# SCH_Selectric-Conversion_2024-07-05.net
KiCad netlist of a schematic drawn in EasyEDA
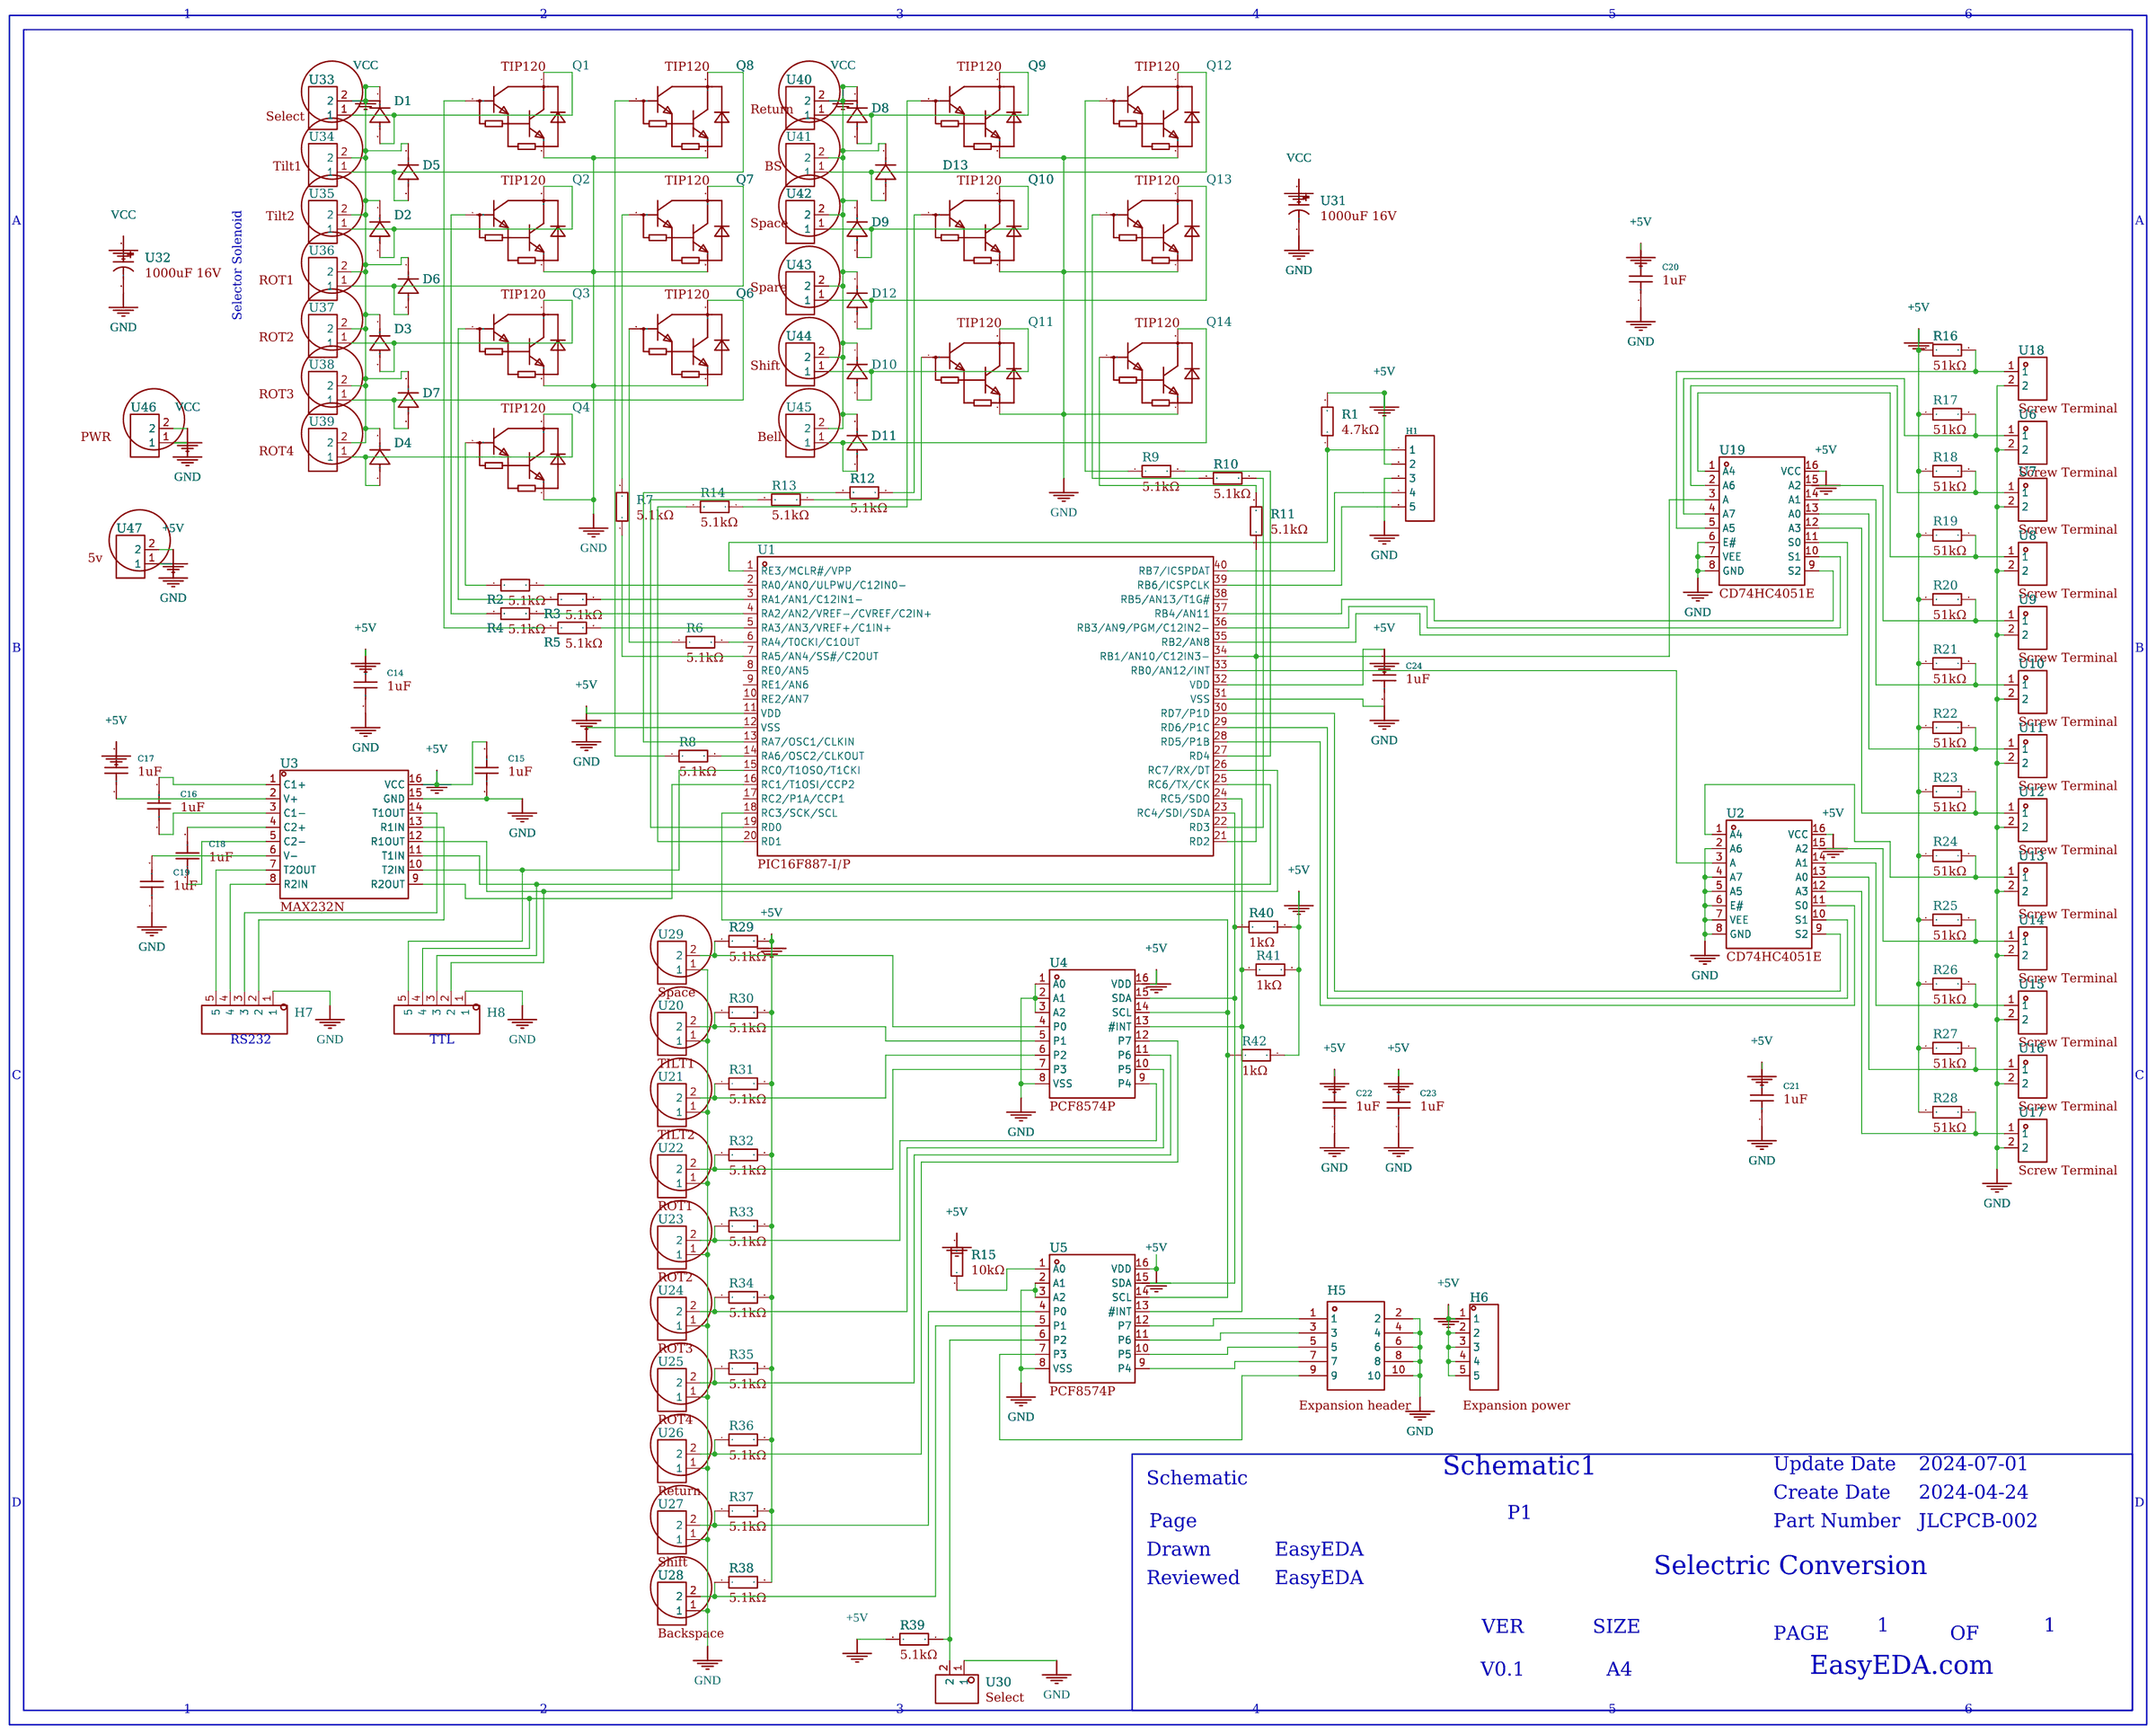
[diagram p0: schematic sheet]

(export (version "E")
  (design (tool "Eeschema 10.0.6"))
  (components
    (comp (ref "C14")
      (value "1uF")
      (fields
        (field (name "Manufacturer Part") "CC1H104MC1FD3F6C10MF")
        (field (name "Manufacturer") "Dersonic(德尔创)")
      )
      (libsource (lib "") (part "Unknown_280_-760"))
    )
    (comp (ref "C15")
      (value "1uF")
      (fields
        (field (name "Manufacturer Part") "CC1H104MC1FD3F6C10MF")
        (field (name "Manufacturer") "Dersonic(德尔创)")
      )
      (libsource (lib "") (part "Unknown_365_-700"))
    )
    (comp (ref "C16")
      (value "1uF")
      (fields
        (field (name "Manufacturer Part") "CC1H104MC1FD3F6C10MF")
        (field (name "Manufacturer") "Dersonic(德尔创)")
      )
      (libsource (lib "") (part "Unknown_135_-675"))
    )
    (comp (ref "C17")
      (value "1uF")
      (fields
        (field (name "Manufacturer Part") "CC1H104MC1FD3F6C10MF")
        (field (name "Manufacturer") "Dersonic(德尔创)")
      )
      (libsource (lib "") (part "Unknown_105_-700"))
    )
    (comp (ref "C18")
      (value "1uF")
      (fields
        (field (name "Manufacturer Part") "CC1H104MC1FD3F6C10MF")
        (field (name "Manufacturer") "Dersonic(德尔创)")
      )
      (libsource (lib "") (part "Unknown_155_-640"))
    )
    (comp (ref "C19")
      (value "1uF")
      (fields
        (field (name "Manufacturer Part") "CC1H104MC1FD3F6C10MF")
        (field (name "Manufacturer") "Dersonic(德尔创)")
      )
      (libsource (lib "") (part "Unknown_130_-620"))
    )
    (comp (ref "C20")
      (value "1uF")
      (fields
        (field (name "Manufacturer Part") "CC1H104MC1FD3F6C10MF")
        (field (name "Manufacturer") "Dersonic(德尔创)")
      )
      (libsource (lib "") (part "Unknown_1175_-1045"))
    )
    (comp (ref "C21")
      (value "1uF")
      (fields
        (field (name "Manufacturer Part") "CC1H104MC1FD3F6C10MF")
        (field (name "Manufacturer") "Dersonic(德尔创)")
      )
      (libsource (lib "") (part "Unknown_1260_-470"))
    )
    (comp (ref "C22")
      (value "1uF")
      (fields
        (field (name "Manufacturer Part") "CC1H104MC1FD3F6C10MF")
        (field (name "Manufacturer") "Dersonic(德尔创)")
      )
      (libsource (lib "") (part "Unknown_960_-465"))
    )
    (comp (ref "C23")
      (value "1uF")
      (fields
        (field (name "Manufacturer Part") "CC1H104MC1FD3F6C10MF")
        (field (name "Manufacturer") "Dersonic(德尔创)")
      )
      (libsource (lib "") (part "Unknown_1005_-465"))
    )
    (comp (ref "C24")
      (value "1uF")
      (fields
        (field (name "Manufacturer Part") "CC1H104MC1FD3F6C10MF")
        (field (name "Manufacturer") "Dersonic(德尔创)")
      )
      (libsource (lib "") (part "Unknown_995_-765"))
    )
    (comp (ref "D1") (value "1N4007") (libsource (lib "") (part "Unknown_290_-1160")))
    (comp (ref "D2") (value "1N4007") (libsource (lib "") (part "Unknown_290_-1080")))
    (comp (ref "D3") (value "1N4007") (libsource (lib "") (part "Unknown_290_-1000")))
    (comp (ref "D4") (value "1N4007") (libsource (lib "") (part "Unknown_290_-920")))
    (comp (ref "D5") (value "1N4007") (libsource (lib "") (part "Unknown_310_-1120")))
    (comp (ref "D6") (value "1N4007") (libsource (lib "") (part "Unknown_310_-1040")))
    (comp (ref "D7") (value "1N4007") (libsource (lib "") (part "Unknown_310_-960")))
    (comp (ref "D8") (value "1N4007") (libsource (lib "") (part "Unknown_625_-1160")))
    (comp (ref "D9") (value "1N4007") (libsource (lib "") (part "Unknown_625_-1080")))
    (comp (ref "D10") (value "1N4007") (libsource (lib "") (part "Unknown_625_-980")))
    (comp (ref "D11") (value "1N4007") (libsource (lib "") (part "Unknown_625_-930")))
    (comp (ref "D12") (value "1N4007") (libsource (lib "") (part "Unknown_625_-1030")))
    (comp (ref "D13") (value "1N4007") (libsource (lib "") (part "Unknown_645_-1120")))
    (comp (ref "H1")
      (value "HDR-F_2.54_1x5P")
      (fields (field (name "Manufacturer Part") "2.54-1*5P母") (field (name "Manufacturer") "BOOMELE(博穆精密)"))
      (libsource (lib "") (part "Unknown_1015_-905"))
    )
    (comp (ref "H5") (value "Expansion header") (libsource (lib "") (part "Unknown_975_-300")))
    (comp (ref "H6") (value "Expansion power") (libsource (lib "") (part "Unknown_1065_-295")))
    (comp (ref "H7") (value "HDR-M_2.54_1x5P") (libsource (lib "") (part "Unknown_195_-525")))
    (comp (ref "H8") (value "HDR-M_2.54_1x5P") (libsource (lib "") (part "Unknown_330_-525")))
    (comp (ref "Q1")
      (value "TIP120")
      (fields (field (name "Manufacturer") "ST(意法半导体)"))
      (libsource (lib "") (part "Unknown_380_-1160"))
    )
    (comp (ref "Q2")
      (value "TIP120")
      (fields (field (name "Manufacturer") "ST(意法半导体)"))
      (libsource (lib "") (part "Unknown_380_-1080"))
    )
    (comp (ref "Q3")
      (value "TIP120")
      (fields (field (name "Manufacturer") "ST(意法半导体)"))
      (libsource (lib "") (part "Unknown_380_-1000"))
    )
    (comp (ref "Q4")
      (value "TIP120")
      (fields (field (name "Manufacturer") "ST(意法半导体)"))
      (libsource (lib "") (part "Unknown_380_-920"))
    )
    (comp (ref "Q6")
      (value "TIP120")
      (fields (field (name "Manufacturer") "ST(意法半导体)"))
      (libsource (lib "") (part "Unknown_495_-1000"))
    )
    (comp (ref "Q7")
      (value "TIP120")
      (fields (field (name "Manufacturer") "ST(意法半导体)"))
      (libsource (lib "") (part "Unknown_495_-1080"))
    )
    (comp (ref "Q8")
      (value "TIP120")
      (fields (field (name "Manufacturer") "ST(意法半导体)"))
      (libsource (lib "") (part "Unknown_495_-1160"))
    )
    (comp (ref "Q9")
      (value "TIP120")
      (fields (field (name "Manufacturer") "ST(意法半导体)"))
      (libsource (lib "") (part "Unknown_700_-1160"))
    )
    (comp (ref "Q10")
      (value "TIP120")
      (fields (field (name "Manufacturer") "ST(意法半导体)"))
      (libsource (lib "") (part "Unknown_700_-1080"))
    )
    (comp (ref "Q11")
      (value "TIP120")
      (fields (field (name "Manufacturer") "ST(意法半导体)"))
      (libsource (lib "") (part "Unknown_700_-980"))
    )
    (comp (ref "Q12")
      (value "TIP120")
      (fields (field (name "Manufacturer") "ST(意法半导体)"))
      (libsource (lib "") (part "Unknown_825_-1160"))
    )
    (comp (ref "Q13")
      (value "TIP120")
      (fields (field (name "Manufacturer") "ST(意法半导体)"))
      (libsource (lib "") (part "Unknown_825_-1080"))
    )
    (comp (ref "Q14")
      (value "TIP120")
      (fields (field (name "Manufacturer") "ST(意法半导体)"))
      (libsource (lib "") (part "Unknown_825_-980"))
    )
    (comp (ref "R1") (value "4.7kΩ") (libsource (lib "") (part "Unknown_955_-945")))
    (comp (ref "R2") (value "5.1kΩ") (libsource (lib "") (part "Unknown_385_-830")))
    (comp (ref "R3") (value "5.1kΩ") (libsource (lib "") (part "Unknown_425_-820")))
    (comp (ref "R4") (value "5.1kΩ") (libsource (lib "") (part "Unknown_385_-810")))
    (comp (ref "R5") (value "5.1kΩ") (libsource (lib "") (part "Unknown_425_-800")))
    (comp (ref "R6") (value "5.1kΩ") (libsource (lib "") (part "Unknown_515_-790")))
    (comp (ref "R7") (value "5.1kΩ") (libsource (lib "") (part "Unknown_460_-885")))
    (comp (ref "R8") (value "5.1kΩ") (libsource (lib "") (part "Unknown_510_-710")))
    (comp (ref "R9") (value "5.1kΩ") (libsource (lib "") (part "Unknown_835_-910")))
    (comp (ref "R10") (value "5.1kΩ") (libsource (lib "") (part "Unknown_885_-905")))
    (comp (ref "R11") (value "5.1kΩ") (libsource (lib "") (part "Unknown_905_-875")))
    (comp (ref "R12") (value "5.1kΩ") (libsource (lib "") (part "Unknown_630_-895")))
    (comp (ref "R13") (value "5.1kΩ") (libsource (lib "") (part "Unknown_575_-890")))
    (comp (ref "R14") (value "5.1kΩ") (libsource (lib "") (part "Unknown_525_-885")))
    (comp (ref "R15") (value "10kΩ") (libsource (lib "") (part "Unknown_695_-355")))
    (comp (ref "R16") (value "51kΩ") (libsource (lib "") (part "Unknown_1390_-995")))
    (comp (ref "R17") (value "51kΩ") (libsource (lib "") (part "Unknown_1390_-950")))
    (comp (ref "R18") (value "51kΩ") (libsource (lib "") (part "Unknown_1390_-910")))
    (comp (ref "R19") (value "51kΩ") (libsource (lib "") (part "Unknown_1390_-865")))
    (comp (ref "R20") (value "51kΩ") (libsource (lib "") (part "Unknown_1390_-820")))
    (comp (ref "R21") (value "51kΩ") (libsource (lib "") (part "Unknown_1390_-775")))
    (comp (ref "R22") (value "51kΩ") (libsource (lib "") (part "Unknown_1390_-730")))
    (comp (ref "R23") (value "51kΩ") (libsource (lib "") (part "Unknown_1390_-685")))
    (comp (ref "R24") (value "51kΩ") (libsource (lib "") (part "Unknown_1390_-640")))
    (comp (ref "R25") (value "51kΩ") (libsource (lib "") (part "Unknown_1390_-595")))
    (comp (ref "R26") (value "51kΩ") (libsource (lib "") (part "Unknown_1390_-550")))
    (comp (ref "R27") (value "51kΩ") (libsource (lib "") (part "Unknown_1390_-505")))
    (comp (ref "R28") (value "51kΩ") (libsource (lib "") (part "Unknown_1390_-460")))
    (comp (ref "R29") (value "5.1kΩ") (libsource (lib "") (part "Unknown_545_-580")))
    (comp (ref "R30") (value "5.1kΩ") (libsource (lib "") (part "Unknown_545_-530")))
    (comp (ref "R31") (value "5.1kΩ") (libsource (lib "") (part "Unknown_545_-480")))
    (comp (ref "R32") (value "5.1kΩ") (libsource (lib "") (part "Unknown_545_-430")))
    (comp (ref "R33") (value "5.1kΩ") (libsource (lib "") (part "Unknown_545_-380")))
    (comp (ref "R34") (value "5.1kΩ") (libsource (lib "") (part "Unknown_545_-330")))
    (comp (ref "R35") (value "5.1kΩ") (libsource (lib "") (part "Unknown_545_-280")))
    (comp (ref "R36") (value "5.1kΩ") (libsource (lib "") (part "Unknown_545_-230")))
    (comp (ref "R37") (value "5.1kΩ") (libsource (lib "") (part "Unknown_545_-180")))
    (comp (ref "R38") (value "5.1kΩ") (libsource (lib "") (part "Unknown_545_-130")))
    (comp (ref "R39") (value "5.1kΩ") (libsource (lib "") (part "Unknown_665_-90")))
    (comp (ref "R40") (value "1kΩ") (libsource (lib "") (part "Unknown_910_-590")))
    (comp (ref "R41") (value "1kΩ") (libsource (lib "") (part "Unknown_915_-560")))
    (comp (ref "R42") (value "1kΩ") (libsource (lib "") (part "Unknown_905_-500")))
    (comp (ref "U1")
      (value "PIC16F887-I/P")
      (fields (field (name "Manufacturer") "MICROCHIP(美国微芯)"))
      (libsource (lib "") (part "Unknown_715_-745"))
    )
    (comp (ref "U2")
      (value "CD74HC4051E")
      (fields (field (name "Manufacturer") "TI(德州仪器)"))
      (libsource (lib "") (part "Unknown_1265_-620"))
    )
    (comp (ref "U3")
      (value "MAX232N")
      (fields (field (name "Manufacturer") "TI(德州仪器)"))
      (libsource (lib "") (part "Unknown_270_-650"))
    )
    (comp (ref "U4")
      (value "PCF8574P")
      (fields (field (name "Manufacturer") "HGSEMI(华冠)"))
      (libsource (lib "") (part "Unknown_790_-515"))
    )
    (comp (ref "U5")
      (value "PCF8574P")
      (fields (field (name "Manufacturer") "HGSEMI(华冠)"))
      (libsource (lib "") (part "Unknown_790_-315"))
    )
    (comp (ref "U6")
      (value "Screw Terminal")
      (fields
        (field (name "Manufacturer Part") "DB128V-5.0-2P-GN-S")
        (field (name "Manufacturer") "DORABO(地博电气)")
      )
      (libsource (lib "") (part "Unknown_1450_-930"))
    )
    (comp (ref "U7")
      (value "Screw Terminal")
      (fields
        (field (name "Manufacturer Part") "DB128V-5.0-2P-GN-S")
        (field (name "Manufacturer") "DORABO(地博电气)")
      )
      (libsource (lib "") (part "Unknown_1450_-890"))
    )
    (comp (ref "U8")
      (value "Screw Terminal")
      (fields
        (field (name "Manufacturer Part") "DB128V-5.0-2P-GN-S")
        (field (name "Manufacturer") "DORABO(地博电气)")
      )
      (libsource (lib "") (part "Unknown_1450_-845"))
    )
    (comp (ref "U9")
      (value "Screw Terminal")
      (fields
        (field (name "Manufacturer Part") "DB128V-5.0-2P-GN-S")
        (field (name "Manufacturer") "DORABO(地博电气)")
      )
      (libsource (lib "") (part "Unknown_1450_-800"))
    )
    (comp (ref "U10")
      (value "Screw Terminal")
      (fields
        (field (name "Manufacturer Part") "DB128V-5.0-2P-GN-S")
        (field (name "Manufacturer") "DORABO(地博电气)")
      )
      (libsource (lib "") (part "Unknown_1450_-755"))
    )
    (comp (ref "U11")
      (value "Screw Terminal")
      (fields
        (field (name "Manufacturer Part") "DB128V-5.0-2P-GN-S")
        (field (name "Manufacturer") "DORABO(地博电气)")
      )
      (libsource (lib "") (part "Unknown_1450_-710"))
    )
    (comp (ref "U12")
      (value "Screw Terminal")
      (fields
        (field (name "Manufacturer Part") "DB128V-5.0-2P-GN-S")
        (field (name "Manufacturer") "DORABO(地博电气)")
      )
      (libsource (lib "") (part "Unknown_1450_-665"))
    )
    (comp (ref "U13")
      (value "Screw Terminal")
      (fields
        (field (name "Manufacturer Part") "DB128V-5.0-2P-GN-S")
        (field (name "Manufacturer") "DORABO(地博电气)")
      )
      (libsource (lib "") (part "Unknown_1450_-620"))
    )
    (comp (ref "U14")
      (value "Screw Terminal")
      (fields
        (field (name "Manufacturer Part") "DB128V-5.0-2P-GN-S")
        (field (name "Manufacturer") "DORABO(地博电气)")
      )
      (libsource (lib "") (part "Unknown_1450_-575"))
    )
    (comp (ref "U15")
      (value "Screw Terminal")
      (fields
        (field (name "Manufacturer Part") "DB128V-5.0-2P-GN-S")
        (field (name "Manufacturer") "DORABO(地博电气)")
      )
      (libsource (lib "") (part "Unknown_1450_-530"))
    )
    (comp (ref "U16")
      (value "Screw Terminal")
      (fields
        (field (name "Manufacturer Part") "DB128V-5.0-2P-GN-S")
        (field (name "Manufacturer") "DORABO(地博电气)")
      )
      (libsource (lib "") (part "Unknown_1450_-485"))
    )
    (comp (ref "U17")
      (value "Screw Terminal")
      (fields
        (field (name "Manufacturer Part") "DB128V-5.0-2P-GN-S")
        (field (name "Manufacturer") "DORABO(地博电气)")
      )
      (libsource (lib "") (part "Unknown_1450_-440"))
    )
    (comp (ref "U18")
      (value "Screw Terminal")
      (fields
        (field (name "Manufacturer Part") "DB128V-5.0-2P-GN-S")
        (field (name "Manufacturer") "DORABO(地博电气)")
      )
      (libsource (lib "") (part "Unknown_1450_-975"))
    )
    (comp (ref "U19")
      (value "CD74HC4051E")
      (fields (field (name "Manufacturer") "TI(德州仪器)"))
      (libsource (lib "") (part "Unknown_1260_-875"))
    )
    (comp (ref "U20")
      (value "TILT1")
      (fields
        (field (name "Manufacturer Part") "DB128V-5.0-2P-GN-S")
        (field (name "Manufacturer") "DORABO(地博电气)")
      )
      (libsource (lib "") (part "Unknown_495_-515"))
    )
    (comp (ref "U21")
      (value "TILT2")
      (fields
        (field (name "Manufacturer Part") "DB128V-5.0-2P-GN-S")
        (field (name "Manufacturer") "DORABO(地博电气)")
      )
      (libsource (lib "") (part "Unknown_495_-465"))
    )
    (comp (ref "U22")
      (value "ROT1")
      (fields
        (field (name "Manufacturer Part") "DB128V-5.0-2P-GN-S")
        (field (name "Manufacturer") "DORABO(地博电气)")
      )
      (libsource (lib "") (part "Unknown_495_-415"))
    )
    (comp (ref "U23")
      (value "ROT2")
      (fields
        (field (name "Manufacturer Part") "DB128V-5.0-2P-GN-S")
        (field (name "Manufacturer") "DORABO(地博电气)")
      )
      (libsource (lib "") (part "Unknown_495_-365"))
    )
    (comp (ref "U24")
      (value "ROT3")
      (fields
        (field (name "Manufacturer Part") "DB128V-5.0-2P-GN-S")
        (field (name "Manufacturer") "DORABO(地博电气)")
      )
      (libsource (lib "") (part "Unknown_495_-315"))
    )
    (comp (ref "U25")
      (value "ROT4")
      (fields
        (field (name "Manufacturer Part") "DB128V-5.0-2P-GN-S")
        (field (name "Manufacturer") "DORABO(地博电气)")
      )
      (libsource (lib "") (part "Unknown_495_-265"))
    )
    (comp (ref "U26")
      (value "Return")
      (fields
        (field (name "Manufacturer Part") "DB128V-5.0-2P-GN-S")
        (field (name "Manufacturer") "DORABO(地博电气)")
      )
      (libsource (lib "") (part "Unknown_495_-215"))
    )
    (comp (ref "U27")
      (value "Shift")
      (fields
        (field (name "Manufacturer Part") "DB128V-5.0-2P-GN-S")
        (field (name "Manufacturer") "DORABO(地博电气)")
      )
      (libsource (lib "") (part "Unknown_495_-165"))
    )
    (comp (ref "U28")
      (value "Backspace")
      (fields
        (field (name "Manufacturer Part") "DB128V-5.0-2P-GN-S")
        (field (name "Manufacturer") "DORABO(地博电气)")
      )
      (libsource (lib "") (part "Unknown_495_-115"))
    )
    (comp (ref "U29")
      (value "Space")
      (fields
        (field (name "Manufacturer Part") "DB128V-5.0-2P-GN-S")
        (field (name "Manufacturer") "DORABO(地博电气)")
      )
      (libsource (lib "") (part "Unknown_495_-565"))
    )
    (comp (ref "U30")
      (value "Select")
      (fields
        (field (name "Manufacturer Part") "DB128V-5.0-2P-GN-S")
        (field (name "Manufacturer") "DORABO(地博电气)")
      )
      (libsource (lib "") (part "Unknown_695_-55"))
    )
    (comp (ref "U31")
      (value "1000uF 16V")
      (fields (field (name "Manufacturer") "CX(承兴)"))
      (libsource (lib "") (part "Unknown_935_-1095"))
    )
    (comp (ref "U32")
      (value "1000uF 16V")
      (fields (field (name "Manufacturer") "CX(承兴)"))
      (libsource (lib "") (part "Unknown_110_-1055"))
    )
    (comp (ref "U33")
      (value "Select")
      (fields
        (field (name "Manufacturer Part") "DB128V-5.0-2P-GN-S")
        (field (name "Manufacturer") "DORABO(地博电气)")
      )
      (libsource (lib "") (part "Unknown_250_-1165"))
    )
    (comp (ref "U34")
      (value "Tilt1")
      (fields
        (field (name "Manufacturer Part") "DB128V-5.0-2P-GN-S")
        (field (name "Manufacturer") "DORABO(地博电气)")
      )
      (libsource (lib "") (part "Unknown_250_-1125"))
    )
    (comp (ref "U35")
      (value "Tilt2")
      (fields
        (field (name "Manufacturer Part") "DB128V-5.0-2P-GN-S")
        (field (name "Manufacturer") "DORABO(地博电气)")
      )
      (libsource (lib "") (part "Unknown_250_-1085"))
    )
    (comp (ref "U36")
      (value "ROT1")
      (fields
        (field (name "Manufacturer Part") "DB128V-5.0-2P-GN-S")
        (field (name "Manufacturer") "DORABO(地博电气)")
      )
      (libsource (lib "") (part "Unknown_250_-1045"))
    )
    (comp (ref "U37")
      (value "ROT2")
      (fields
        (field (name "Manufacturer Part") "DB128V-5.0-2P-GN-S")
        (field (name "Manufacturer") "DORABO(地博电气)")
      )
      (libsource (lib "") (part "Unknown_250_-1005"))
    )
    (comp (ref "U38")
      (value "ROT3")
      (fields
        (field (name "Manufacturer Part") "DB128V-5.0-2P-GN-S")
        (field (name "Manufacturer") "DORABO(地博电气)")
      )
      (libsource (lib "") (part "Unknown_250_-965"))
    )
    (comp (ref "U39")
      (value "ROT4")
      (fields
        (field (name "Manufacturer Part") "DB128V-5.0-2P-GN-S")
        (field (name "Manufacturer") "DORABO(地博电气)")
      )
      (libsource (lib "") (part "Unknown_250_-925"))
    )
    (comp (ref "U40")
      (value "Return")
      (fields
        (field (name "Manufacturer Part") "DB128V-5.0-2P-GN-S")
        (field (name "Manufacturer") "DORABO(地博电气)")
      )
      (libsource (lib "") (part "Unknown_585_-1165"))
    )
    (comp (ref "U41")
      (value "BS")
      (fields
        (field (name "Manufacturer Part") "DB128V-5.0-2P-GN-S")
        (field (name "Manufacturer") "DORABO(地博电气)")
      )
      (libsource (lib "") (part "Unknown_585_-1125"))
    )
    (comp (ref "U42")
      (value "Space")
      (fields
        (field (name "Manufacturer Part") "DB128V-5.0-2P-GN-S")
        (field (name "Manufacturer") "DORABO(地博电气)")
      )
      (libsource (lib "") (part "Unknown_585_-1085"))
    )
    (comp (ref "U43")
      (value "Spare")
      (fields
        (field (name "Manufacturer Part") "DB128V-5.0-2P-GN-S")
        (field (name "Manufacturer") "DORABO(地博电气)")
      )
      (libsource (lib "") (part "Unknown_585_-1035"))
    )
    (comp (ref "U44")
      (value "Shift")
      (fields
        (field (name "Manufacturer Part") "DB128V-5.0-2P-GN-S")
        (field (name "Manufacturer") "DORABO(地博电气)")
      )
      (libsource (lib "") (part "Unknown_585_-985"))
    )
    (comp (ref "U45")
      (value "Bell")
      (fields
        (field (name "Manufacturer Part") "DB128V-5.0-2P-GN-S")
        (field (name "Manufacturer") "DORABO(地博电气)")
      )
      (libsource (lib "") (part "Unknown_585_-935"))
    )
    (comp (ref "U46")
      (value "PWR")
      (fields
        (field (name "Manufacturer Part") "DB128V-5.0-2P-GN-S")
        (field (name "Manufacturer") "DORABO(地博电气)")
      )
      (libsource (lib "") (part "Unknown_125_-935"))
    )
    (comp (ref "U47")
      (value "5v")
      (fields
        (field (name "Manufacturer Part") "DB128V-5.0-2P-GN-S")
        (field (name "Manufacturer") "DORABO(地博电气)")
      )
      (libsource (lib "") (part "Unknown_115_-850"))
    )
  )
  (nets
    (net (code "1") (name "+5V") (class "Default")
      (node (ref "C14") (pin "2") (pinfunction "2_2") (pintype "unspecified"))
      (node (ref "C15") (pin "2") (pinfunction "2_2") (pintype "unspecified"))
      (node (ref "C17") (pin "2") (pinfunction "2_2") (pintype "unspecified"))
      (node (ref "C20") (pin "2") (pinfunction "2_2") (pintype "unspecified"))
      (node (ref "C21") (pin "2") (pinfunction "2_2") (pintype "unspecified"))
      (node (ref "C22") (pin "2") (pinfunction "2_2") (pintype "unspecified"))
      (node (ref "C23") (pin "2") (pinfunction "2_2") (pintype "unspecified"))
      (node (ref "C24") (pin "2") (pinfunction "2_2") (pintype "unspecified"))
      (node (ref "H1") (pin "2") (pinfunction "2_2") (pintype "unspecified"))
      (node (ref "H6") (pin "1") (pinfunction "1_1") (pintype "unspecified"))
      (node (ref "H6") (pin "2") (pinfunction "2_2") (pintype "unspecified"))
      (node (ref "H6") (pin "3") (pinfunction "3_3") (pintype "unspecified"))
      (node (ref "H6") (pin "4") (pinfunction "4_4") (pintype "unspecified"))
      (node (ref "H6") (pin "5") (pinfunction "5_5") (pintype "unspecified"))
      (node (ref "R1") (pin "2") (pinfunction "2_2") (pintype "unspecified"))
      (node (ref "R15") (pin "2") (pinfunction "2_2") (pintype "unspecified"))
      (node (ref "R16") (pin "1") (pinfunction "1_1") (pintype "unspecified"))
      (node (ref "R17") (pin "1") (pinfunction "1_1") (pintype "unspecified"))
      (node (ref "R18") (pin "1") (pinfunction "1_1") (pintype "unspecified"))
      (node (ref "R19") (pin "1") (pinfunction "1_1") (pintype "unspecified"))
      (node (ref "R20") (pin "1") (pinfunction "1_1") (pintype "unspecified"))
      (node (ref "R21") (pin "1") (pinfunction "1_1") (pintype "unspecified"))
      (node (ref "R22") (pin "1") (pinfunction "1_1") (pintype "unspecified"))
      (node (ref "R23") (pin "1") (pinfunction "1_1") (pintype "unspecified"))
      (node (ref "R24") (pin "1") (pinfunction "1_1") (pintype "unspecified"))
      (node (ref "R25") (pin "1") (pinfunction "1_1") (pintype "unspecified"))
      (node (ref "R26") (pin "1") (pinfunction "1_1") (pintype "unspecified"))
      (node (ref "R27") (pin "1") (pinfunction "1_1") (pintype "unspecified"))
      (node (ref "R28") (pin "1") (pinfunction "1_1") (pintype "unspecified"))
      (node (ref "R29") (pin "2") (pinfunction "2_2") (pintype "unspecified"))
      (node (ref "R30") (pin "2") (pinfunction "2_2") (pintype "unspecified"))
      (node (ref "R31") (pin "2") (pinfunction "2_2") (pintype "unspecified"))
      (node (ref "R32") (pin "2") (pinfunction "2_2") (pintype "unspecified"))
      (node (ref "R33") (pin "2") (pinfunction "2_2") (pintype "unspecified"))
      (node (ref "R34") (pin "2") (pinfunction "2_2") (pintype "unspecified"))
      (node (ref "R35") (pin "2") (pinfunction "2_2") (pintype "unspecified"))
      (node (ref "R36") (pin "2") (pinfunction "2_2") (pintype "unspecified"))
      (node (ref "R37") (pin "2") (pinfunction "2_2") (pintype "unspecified"))
      (node (ref "R38") (pin "2") (pinfunction "2_2") (pintype "unspecified"))
      (node (ref "R39") (pin "1") (pinfunction "1_1") (pintype "unspecified"))
      (node (ref "R40") (pin "2") (pinfunction "2_2") (pintype "unspecified"))
      (node (ref "R41") (pin "2") (pinfunction "2_2") (pintype "unspecified"))
      (node (ref "R42") (pin "2") (pinfunction "2_2") (pintype "unspecified"))
      (node (ref "U1") (pin "11") (pinfunction "VDD_11") (pintype "unspecified"))
      (node (ref "U1") (pin "32") (pinfunction "VDD_32") (pintype "unspecified"))
      (node (ref "U19") (pin "16") (pinfunction "VCC_16") (pintype "unspecified"))
      (node (ref "U2") (pin "16") (pinfunction "VCC_16") (pintype "unspecified"))
      (node (ref "U3") (pin "16") (pinfunction "VCC_16") (pintype "unspecified"))
      (node (ref "U4") (pin "16") (pinfunction "VDD_16") (pintype "unspecified"))
      (node (ref "U47") (pin "2") (pinfunction "2_2") (pintype "unspecified"))
      (node (ref "U5") (pin "16") (pinfunction "VDD_16") (pintype "unspecified"))
    )
    (net (code "2") (name "GND") (class "Default")
      (node (ref "C14") (pin "1") (pinfunction "1_1") (pintype "unspecified"))
      (node (ref "C15") (pin "1") (pinfunction "1_1") (pintype "unspecified"))
      (node (ref "C19") (pin "1") (pinfunction "1_1") (pintype "unspecified"))
      (node (ref "C20") (pin "1") (pinfunction "1_1") (pintype "unspecified"))
      (node (ref "C21") (pin "1") (pinfunction "1_1") (pintype "unspecified"))
      (node (ref "C22") (pin "1") (pinfunction "1_1") (pintype "unspecified"))
      (node (ref "C23") (pin "1") (pinfunction "1_1") (pintype "unspecified"))
      (node (ref "C24") (pin "1") (pinfunction "1_1") (pintype "unspecified"))
      (node (ref "H1") (pin "3") (pinfunction "3_3") (pintype "unspecified"))
      (node (ref "H5") (pin "10") (pinfunction "10_10") (pintype "unspecified"))
      (node (ref "H5") (pin "2") (pinfunction "2_2") (pintype "unspecified"))
      (node (ref "H5") (pin "4") (pinfunction "4_4") (pintype "unspecified"))
      (node (ref "H5") (pin "6") (pinfunction "6_6") (pintype "unspecified"))
      (node (ref "H5") (pin "8") (pinfunction "8_8") (pintype "unspecified"))
      (node (ref "H7") (pin "1") (pinfunction "1_1") (pintype "unspecified"))
      (node (ref "H8") (pin "1") (pinfunction "1_1") (pintype "unspecified"))
      (node (ref "Q1") (pin "3") (pinfunction "E_3") (pintype "unspecified"))
      (node (ref "Q10") (pin "3") (pinfunction "E_3") (pintype "unspecified"))
      (node (ref "Q11") (pin "3") (pinfunction "E_3") (pintype "unspecified"))
      (node (ref "Q12") (pin "3") (pinfunction "E_3") (pintype "unspecified"))
      (node (ref "Q13") (pin "3") (pinfunction "E_3") (pintype "unspecified"))
      (node (ref "Q14") (pin "3") (pinfunction "E_3") (pintype "unspecified"))
      (node (ref "Q2") (pin "3") (pinfunction "E_3") (pintype "unspecified"))
      (node (ref "Q3") (pin "3") (pinfunction "E_3") (pintype "unspecified"))
      (node (ref "Q4") (pin "3") (pinfunction "E_3") (pintype "unspecified"))
      (node (ref "Q6") (pin "3") (pinfunction "E_3") (pintype "unspecified"))
      (node (ref "Q7") (pin "3") (pinfunction "E_3") (pintype "unspecified"))
      (node (ref "Q8") (pin "3") (pinfunction "E_3") (pintype "unspecified"))
      (node (ref "Q9") (pin "3") (pinfunction "E_3") (pintype "unspecified"))
      (node (ref "U1") (pin "12") (pinfunction "VSS_12") (pintype "unspecified"))
      (node (ref "U1") (pin "31") (pinfunction "VSS_31") (pintype "unspecified"))
      (node (ref "U10") (pin "2") (pinfunction "2_2") (pintype "unspecified"))
      (node (ref "U11") (pin "2") (pinfunction "2_2") (pintype "unspecified"))
      (node (ref "U12") (pin "2") (pinfunction "2_2") (pintype "unspecified"))
      (node (ref "U13") (pin "2") (pinfunction "2_2") (pintype "unspecified"))
      (node (ref "U14") (pin "2") (pinfunction "2_2") (pintype "unspecified"))
      (node (ref "U15") (pin "2") (pinfunction "2_2") (pintype "unspecified"))
      (node (ref "U16") (pin "2") (pinfunction "2_2") (pintype "unspecified"))
      (node (ref "U17") (pin "2") (pinfunction "2_2") (pintype "unspecified"))
      (node (ref "U18") (pin "2") (pinfunction "2_2") (pintype "unspecified"))
      (node (ref "U19") (pin "6") (pinfunction "E#_6") (pintype "unspecified"))
      (node (ref "U19") (pin "7") (pinfunction "VEE_7") (pintype "unspecified"))
      (node (ref "U19") (pin "8") (pinfunction "GND_8") (pintype "unspecified"))
      (node (ref "U2") (pin "2") (pinfunction "A6_2") (pintype "unspecified"))
      (node (ref "U2") (pin "4") (pinfunction "A7_4") (pintype "unspecified"))
      (node (ref "U2") (pin "5") (pinfunction "A5_5") (pintype "unspecified"))
      (node (ref "U2") (pin "6") (pinfunction "E#_6") (pintype "unspecified"))
      (node (ref "U2") (pin "7") (pinfunction "VEE_7") (pintype "unspecified"))
      (node (ref "U2") (pin "8") (pinfunction "GND_8") (pintype "unspecified"))
      (node (ref "U20") (pin "1") (pinfunction "1_1") (pintype "unspecified"))
      (node (ref "U21") (pin "1") (pinfunction "1_1") (pintype "unspecified"))
      (node (ref "U22") (pin "1") (pinfunction "1_1") (pintype "unspecified"))
      (node (ref "U23") (pin "1") (pinfunction "1_1") (pintype "unspecified"))
      (node (ref "U24") (pin "1") (pinfunction "1_1") (pintype "unspecified"))
      (node (ref "U25") (pin "1") (pinfunction "1_1") (pintype "unspecified"))
      (node (ref "U26") (pin "1") (pinfunction "1_1") (pintype "unspecified"))
      (node (ref "U27") (pin "1") (pinfunction "1_1") (pintype "unspecified"))
      (node (ref "U28") (pin "1") (pinfunction "1_1") (pintype "unspecified"))
      (node (ref "U29") (pin "1") (pinfunction "1_1") (pintype "unspecified"))
      (node (ref "U3") (pin "15") (pinfunction "GND_15") (pintype "unspecified"))
      (node (ref "U30") (pin "1") (pinfunction "1_1") (pintype "unspecified"))
      (node (ref "U31") (pin "2") (pinfunction "2_2") (pintype "unspecified"))
      (node (ref "U32") (pin "2") (pinfunction "2_2") (pintype "unspecified"))
      (node (ref "U4") (pin "1") (pinfunction "A0_1") (pintype "unspecified"))
      (node (ref "U4") (pin "2") (pinfunction "A1_2") (pintype "unspecified"))
      (node (ref "U4") (pin "3") (pinfunction "A2_3") (pintype "unspecified"))
      (node (ref "U4") (pin "8") (pinfunction "VSS_8") (pintype "unspecified"))
      (node (ref "U46") (pin "1") (pinfunction "1_1") (pintype "unspecified"))
      (node (ref "U47") (pin "1") (pinfunction "1_1") (pintype "unspecified"))
      (node (ref "U5") (pin "2") (pinfunction "A1_2") (pintype "unspecified"))
      (node (ref "U5") (pin "3") (pinfunction "A2_3") (pintype "unspecified"))
      (node (ref "U5") (pin "8") (pinfunction "VSS_8") (pintype "unspecified"))
      (node (ref "U6") (pin "2") (pinfunction "2_2") (pintype "unspecified"))
      (node (ref "U7") (pin "2") (pinfunction "2_2") (pintype "unspecified"))
      (node (ref "U8") (pin "2") (pinfunction "2_2") (pintype "unspecified"))
      (node (ref "U9") (pin "2") (pinfunction "2_2") (pintype "unspecified"))
    )
    (net (code "3") (name "Net-(D1-A)") (class "Default")
      (node (ref "D1") (pin "2") (pinfunction "A_2") (pintype "unspecified"))
      (node (ref "Q1") (pin "2") (pinfunction "C_2") (pintype "unspecified"))
      (node (ref "U33") (pin "1") (pinfunction "1_1") (pintype "unspecified"))
    )
    (net (code "4") (name "Net-(D2-A)") (class "Default")
      (node (ref "D2") (pin "2") (pinfunction "A_2") (pintype "unspecified"))
      (node (ref "Q2") (pin "2") (pinfunction "C_2") (pintype "unspecified"))
      (node (ref "U35") (pin "1") (pinfunction "1_1") (pintype "unspecified"))
    )
    (net (code "5") (name "Net-(D3-A)") (class "Default")
      (node (ref "D3") (pin "2") (pinfunction "A_2") (pintype "unspecified"))
      (node (ref "Q3") (pin "2") (pinfunction "C_2") (pintype "unspecified"))
      (node (ref "U37") (pin "1") (pinfunction "1_1") (pintype "unspecified"))
    )
    (net (code "6") (name "Net-(D4-A)") (class "Default")
      (node (ref "D4") (pin "2") (pinfunction "A_2") (pintype "unspecified"))
      (node (ref "Q4") (pin "2") (pinfunction "C_2") (pintype "unspecified"))
      (node (ref "U39") (pin "1") (pinfunction "1_1") (pintype "unspecified"))
    )
    (net (code "7") (name "Net-(D5-A)") (class "Default")
      (node (ref "D5") (pin "2") (pinfunction "A_2") (pintype "unspecified"))
      (node (ref "Q8") (pin "2") (pinfunction "C_2") (pintype "unspecified"))
      (node (ref "U34") (pin "1") (pinfunction "1_1") (pintype "unspecified"))
    )
    (net (code "8") (name "Net-(D6-A)") (class "Default")
      (node (ref "D6") (pin "2") (pinfunction "A_2") (pintype "unspecified"))
      (node (ref "Q7") (pin "2") (pinfunction "C_2") (pintype "unspecified"))
      (node (ref "U36") (pin "1") (pinfunction "1_1") (pintype "unspecified"))
    )
    (net (code "9") (name "Net-(D7-A)") (class "Default")
      (node (ref "D7") (pin "2") (pinfunction "A_2") (pintype "unspecified"))
      (node (ref "Q6") (pin "2") (pinfunction "C_2") (pintype "unspecified"))
      (node (ref "U38") (pin "1") (pinfunction "1_1") (pintype "unspecified"))
    )
    (net (code "10") (name "Net-(D8-A)") (class "Default")
      (node (ref "D8") (pin "2") (pinfunction "A_2") (pintype "unspecified"))
      (node (ref "Q9") (pin "2") (pinfunction "C_2") (pintype "unspecified"))
      (node (ref "U40") (pin "1") (pinfunction "1_1") (pintype "unspecified"))
    )
    (net (code "11") (name "Net-(D9-A)") (class "Default")
      (node (ref "D9") (pin "2") (pinfunction "A_2") (pintype "unspecified"))
      (node (ref "Q10") (pin "2") (pinfunction "C_2") (pintype "unspecified"))
      (node (ref "U42") (pin "1") (pinfunction "1_1") (pintype "unspecified"))
    )
    (net (code "12") (name "Net-(D10-A)") (class "Default")
      (node (ref "D10") (pin "2") (pinfunction "A_2") (pintype "unspecified"))
      (node (ref "Q11") (pin "2") (pinfunction "C_2") (pintype "unspecified"))
      (node (ref "U44") (pin "1") (pinfunction "1_1") (pintype "unspecified"))
    )
    (net (code "13") (name "Net-(D11-A)") (class "Default")
      (node (ref "D11") (pin "2") (pinfunction "A_2") (pintype "unspecified"))
      (node (ref "Q14") (pin "2") (pinfunction "C_2") (pintype "unspecified"))
      (node (ref "U45") (pin "1") (pinfunction "1_1") (pintype "unspecified"))
    )
    (net (code "14") (name "Net-(D12-A)") (class "Default")
      (node (ref "D12") (pin "2") (pinfunction "A_2") (pintype "unspecified"))
      (node (ref "Q13") (pin "2") (pinfunction "C_2") (pintype "unspecified"))
      (node (ref "U43") (pin "1") (pinfunction "1_1") (pintype "unspecified"))
    )
    (net (code "15") (name "Net-(D13-A)") (class "Default")
      (node (ref "D13") (pin "2") (pinfunction "A_2") (pintype "unspecified"))
      (node (ref "Q12") (pin "2") (pinfunction "C_2") (pintype "unspecified"))
      (node (ref "U41") (pin "1") (pinfunction "1_1") (pintype "unspecified"))
    )
    (net (code "16") (name "Net-(Q1-B)") (class "Default")
      (node (ref "Q1") (pin "1") (pinfunction "B_1") (pintype "unspecified"))
      (node (ref "R5") (pin "1") (pinfunction "1_1") (pintype "unspecified"))
    )
    (net (code "17") (name "Net-(Q2-B)") (class "Default")
      (node (ref "Q2") (pin "1") (pinfunction "B_1") (pintype "unspecified"))
      (node (ref "R4") (pin "1") (pinfunction "1_1") (pintype "unspecified"))
    )
    (net (code "18") (name "Net-(Q3-B)") (class "Default")
      (node (ref "Q3") (pin "1") (pinfunction "B_1") (pintype "unspecified"))
      (node (ref "R3") (pin "1") (pinfunction "1_1") (pintype "unspecified"))
    )
    (net (code "19") (name "Net-(Q4-B)") (class "Default")
      (node (ref "Q4") (pin "1") (pinfunction "B_1") (pintype "unspecified"))
      (node (ref "R2") (pin "1") (pinfunction "1_1") (pintype "unspecified"))
    )
    (net (code "20") (name "Net-(Q6-B)") (class "Default")
      (node (ref "Q6") (pin "1") (pinfunction "B_1") (pintype "unspecified"))
      (node (ref "R6") (pin "1") (pinfunction "1_1") (pintype "unspecified"))
    )
    (net (code "21") (name "Net-(Q7-B)") (class "Default")
      (node (ref "Q7") (pin "1") (pinfunction "B_1") (pintype "unspecified"))
      (node (ref "R7") (pin "2") (pinfunction "2_2") (pintype "unspecified"))
    )
    (net (code "22") (name "Net-(Q8-B)") (class "Default")
      (node (ref "Q8") (pin "1") (pinfunction "B_1") (pintype "unspecified"))
      (node (ref "R8") (pin "1") (pinfunction "1_1") (pintype "unspecified"))
    )
    (net (code "23") (name "Net-(Q9-B)") (class "Default")
      (node (ref "Q9") (pin "1") (pinfunction "B_1") (pintype "unspecified"))
      (node (ref "R14") (pin "1") (pinfunction "1_1") (pintype "unspecified"))
    )
    (net (code "24") (name "Net-(Q10-B)") (class "Default")
      (node (ref "Q10") (pin "1") (pinfunction "B_1") (pintype "unspecified"))
      (node (ref "R12") (pin "1") (pinfunction "1_1") (pintype "unspecified"))
    )
    (net (code "25") (name "Net-(Q11-B)") (class "Default")
      (node (ref "Q11") (pin "1") (pinfunction "B_1") (pintype "unspecified"))
      (node (ref "R13") (pin "1") (pinfunction "1_1") (pintype "unspecified"))
    )
    (net (code "26") (name "Net-(Q12-B)") (class "Default")
      (node (ref "Q12") (pin "1") (pinfunction "B_1") (pintype "unspecified"))
      (node (ref "R9") (pin "1") (pinfunction "1_1") (pintype "unspecified"))
    )
    (net (code "27") (name "Net-(Q13-B)") (class "Default")
      (node (ref "Q13") (pin "1") (pinfunction "B_1") (pintype "unspecified"))
      (node (ref "R10") (pin "1") (pinfunction "1_1") (pintype "unspecified"))
    )
    (net (code "28") (name "Net-(Q14-B)") (class "Default")
      (node (ref "Q14") (pin "1") (pinfunction "B_1") (pintype "unspecified"))
      (node (ref "R11") (pin "2") (pinfunction "2_2") (pintype "unspecified"))
    )
    (net (code "29") (name "Net-(U1-RA0{slash}AN0{slash}ULPWU{slash}C12IN0-)") (class "Default")
      (node (ref "R2") (pin "2") (pinfunction "2_2") (pintype "unspecified"))
      (node (ref "U1") (pin "2") (pinfunction "RA0/AN0/ULPWU/C12IN0-_2") (pintype "unspecified"))
    )
    (net (code "30") (name "Net-(U1-RA1{slash}AN1{slash}C12IN1-)") (class "Default")
      (node (ref "R3") (pin "2") (pinfunction "2_2") (pintype "unspecified"))
      (node (ref "U1") (pin "3") (pinfunction "RA1/AN1/C12IN1-_3") (pintype "unspecified"))
    )
    (net (code "31") (name "Net-(U1-RA2{slash}AN2{slash}VREF-{slash}CVREF{slash}C2IN+)") (class "Default")
      (node (ref "R4") (pin "2") (pinfunction "2_2") (pintype "unspecified"))
      (node (ref "U1") (pin "4") (pinfunction "RA2/AN2/VREF-/CVREF/C2IN+_4") (pintype "unspecified"))
    )
    (net (code "32") (name "Net-(U1-RA3{slash}AN3{slash}VREF+{slash}C1IN+)") (class "Default")
      (node (ref "R5") (pin "2") (pinfunction "2_2") (pintype "unspecified"))
      (node (ref "U1") (pin "5") (pinfunction "RA3/AN3/VREF+/C1IN+_5") (pintype "unspecified"))
    )
    (net (code "33") (name "Net-(U1-RA4{slash}T0CKI{slash}C1OUT)") (class "Default")
      (node (ref "R6") (pin "2") (pinfunction "2_2") (pintype "unspecified"))
      (node (ref "U1") (pin "6") (pinfunction "RA4/T0CKI/C1OUT_6") (pintype "unspecified"))
    )
    (net (code "34") (name "Net-(U1-RA5{slash}AN4{slash}SS#{slash}C2OUT)") (class "Default")
      (node (ref "R7") (pin "1") (pinfunction "1_1") (pintype "unspecified"))
      (node (ref "U1") (pin "7") (pinfunction "RA5/AN4/SS#/C2OUT_7") (pintype "unspecified"))
    )
    (net (code "35") (name "Net-(U1-RA6{slash}OSC2{slash}CLKOUT)") (class "Default")
      (node (ref "R8") (pin "2") (pinfunction "2_2") (pintype "unspecified"))
      (node (ref "U1") (pin "14") (pinfunction "RA6/OSC2/CLKOUT_14") (pintype "unspecified"))
    )
    (net (code "36") (name "Net-(U1-RA7{slash}OSC1{slash}CLKIN)") (class "Default")
      (node (ref "R12") (pin "2") (pinfunction "2_2") (pintype "unspecified"))
      (node (ref "U1") (pin "13") (pinfunction "RA7/OSC1/CLKIN_13") (pintype "unspecified"))
    )
    (net (code "37") (name "Net-(U1-RB0{slash}AN12{slash}INT)") (class "Default")
      (node (ref "U1") (pin "33") (pinfunction "RB0/AN12/INT_33") (pintype "unspecified"))
      (node (ref "U2") (pin "3") (pinfunction "A_3") (pintype "unspecified"))
    )
    (net (code "38") (name "Net-(U1-RB1{slash}AN10{slash}C12IN3-)") (class "Default")
      (node (ref "R11") (pin "1") (pinfunction "1_1") (pintype "unspecified"))
      (node (ref "U1") (pin "21") (pinfunction "RD2_21") (pintype "unspecified"))
      (node (ref "U1") (pin "34") (pinfunction "RB1/AN10/C12IN3-_34") (pintype "unspecified"))
      (node (ref "U19") (pin "3") (pinfunction "A_3") (pintype "unspecified"))
    )
    (net (code "39") (name "Net-(U1-RB2{slash}AN8)") (class "Default")
      (node (ref "U1") (pin "35") (pinfunction "RB2/AN8_35") (pintype "unspecified"))
      (node (ref "U19") (pin "11") (pinfunction "S0_11") (pintype "unspecified"))
    )
    (net (code "40") (name "Net-(U1-RB3{slash}AN9{slash}PGM{slash}C12IN2-)") (class "Default")
      (node (ref "U1") (pin "36") (pinfunction "RB3/AN9/PGM/C12IN2-_36") (pintype "unspecified"))
      (node (ref "U19") (pin "10") (pinfunction "S1_10") (pintype "unspecified"))
    )
    (net (code "41") (name "Net-(U1-RB4{slash}AN11)") (class "Default")
      (node (ref "U1") (pin "37") (pinfunction "RB4/AN11_37") (pintype "unspecified"))
      (node (ref "U19") (pin "9") (pinfunction "S2_9") (pintype "unspecified"))
    )
    (net (code "42") (name "Net-(U1-RB6{slash}ICSPCLK)") (class "Default")
      (node (ref "H1") (pin "5") (pinfunction "5_5") (pintype "unspecified"))
      (node (ref "U1") (pin "39") (pinfunction "RB6/ICSPCLK_39") (pintype "unspecified"))
    )
    (net (code "43") (name "Net-(U1-RB7{slash}ICSPDAT)") (class "Default")
      (node (ref "H1") (pin "4") (pinfunction "4_4") (pintype "unspecified"))
      (node (ref "U1") (pin "40") (pinfunction "RB7/ICSPDAT_40") (pintype "unspecified"))
    )
    (net (code "44") (name "Net-(U1-RC0{slash}T1OSO{slash}T1CKI)") (class "Default")
      (node (ref "H8") (pin "5") (pinfunction "5_5") (pintype "unspecified"))
      (node (ref "U1") (pin "15") (pinfunction "RC0/T1OSO/T1CKI_15") (pintype "unspecified"))
      (node (ref "U3") (pin "10") (pinfunction "T2IN_10") (pintype "unspecified"))
    )
    (net (code "45") (name "Net-(U1-RC1{slash}T1OSI{slash}CCP2)") (class "Default")
      (node (ref "H8") (pin "4") (pinfunction "4_4") (pintype "unspecified"))
      (node (ref "U1") (pin "16") (pinfunction "RC1/T1OSI/CCP2_16") (pintype "unspecified"))
      (node (ref "U3") (pin "9") (pinfunction "R2OUT_9") (pintype "unspecified"))
    )
    (net (code "46") (name "Net-(U1-RC3{slash}SCK{slash}SCL)") (class "Default")
      (node (ref "R42") (pin "1") (pinfunction "1_1") (pintype "unspecified"))
      (node (ref "U1") (pin "18") (pinfunction "RC3/SCK/SCL_18") (pintype "unspecified"))
      (node (ref "U4") (pin "14") (pinfunction "SCL_14") (pintype "unspecified"))
      (node (ref "U5") (pin "14") (pinfunction "SCL_14") (pintype "unspecified"))
    )
    (net (code "47") (name "Net-(U1-RC4{slash}SDI{slash}SDA)") (class "Default")
      (node (ref "R40") (pin "1") (pinfunction "1_1") (pintype "unspecified"))
      (node (ref "U1") (pin "23") (pinfunction "RC4/SDI/SDA_23") (pintype "unspecified"))
      (node (ref "U4") (pin "15") (pinfunction "SDA_15") (pintype "unspecified"))
      (node (ref "U5") (pin "15") (pinfunction "SDA_15") (pintype "unspecified"))
    )
    (net (code "48") (name "Net-(U1-RC5{slash}SDO)") (class "Default")
      (node (ref "R41") (pin "1") (pinfunction "1_1") (pintype "unspecified"))
      (node (ref "U1") (pin "24") (pinfunction "RC5/SDO_24") (pintype "unspecified"))
      (node (ref "U4") (pin "13") (pinfunction "#INT_13") (pintype "unspecified"))
      (node (ref "U5") (pin "13") (pinfunction "#INT_13") (pintype "unspecified"))
    )
    (net (code "49") (name "Net-(U1-RC6{slash}TX{slash}CK)") (class "Default")
      (node (ref "H8") (pin "3") (pinfunction "3_3") (pintype "unspecified"))
      (node (ref "U1") (pin "25") (pinfunction "RC6/TX/CK_25") (pintype "unspecified"))
      (node (ref "U3") (pin "11") (pinfunction "T1IN_11") (pintype "unspecified"))
    )
    (net (code "50") (name "Net-(U1-RC7{slash}RX{slash}DT)") (class "Default")
      (node (ref "H8") (pin "2") (pinfunction "2_2") (pintype "unspecified"))
      (node (ref "U1") (pin "26") (pinfunction "RC7/RX/DT_26") (pintype "unspecified"))
      (node (ref "U3") (pin "12") (pinfunction "R1OUT_12") (pintype "unspecified"))
    )
    (net (code "51") (name "Net-(U1-RD0)") (class "Default")
      (node (ref "R13") (pin "2") (pinfunction "2_2") (pintype "unspecified"))
      (node (ref "U1") (pin "19") (pinfunction "RD0_19") (pintype "unspecified"))
    )
    (net (code "52") (name "Net-(U1-RD1)") (class "Default")
      (node (ref "R14") (pin "2") (pinfunction "2_2") (pintype "unspecified"))
      (node (ref "U1") (pin "20") (pinfunction "RD1_20") (pintype "unspecified"))
    )
    (net (code "53") (name "Net-(U1-RD3)") (class "Default")
      (node (ref "R10") (pin "2") (pinfunction "2_2") (pintype "unspecified"))
      (node (ref "U1") (pin "22") (pinfunction "RD3_22") (pintype "unspecified"))
    )
    (net (code "54") (name "Net-(U1-RD4)") (class "Default")
      (node (ref "R9") (pin "2") (pinfunction "2_2") (pintype "unspecified"))
      (node (ref "U1") (pin "27") (pinfunction "RD4_27") (pintype "unspecified"))
    )
    (net (code "55") (name "Net-(U1-RD5{slash}P1B)") (class "Default")
      (node (ref "U1") (pin "28") (pinfunction "RD5/P1B_28") (pintype "unspecified"))
      (node (ref "U2") (pin "11") (pinfunction "S0_11") (pintype "unspecified"))
    )
    (net (code "56") (name "Net-(U1-RD6{slash}P1C)") (class "Default")
      (node (ref "U1") (pin "29") (pinfunction "RD6/P1C_29") (pintype "unspecified"))
      (node (ref "U2") (pin "10") (pinfunction "S1_10") (pintype "unspecified"))
    )
    (net (code "57") (name "Net-(U1-RD7{slash}P1D)") (class "Default")
      (node (ref "U1") (pin "30") (pinfunction "RD7/P1D_30") (pintype "unspecified"))
      (node (ref "U2") (pin "9") (pinfunction "S2_9") (pintype "unspecified"))
    )
    (net (code "58") (name "Net-(U1-RE3{slash}MCLR#{slash}VPP)") (class "Default")
      (node (ref "H1") (pin "1") (pinfunction "1_1") (pintype "unspecified"))
      (node (ref "R1") (pin "1") (pinfunction "1_1") (pintype "unspecified"))
      (node (ref "U1") (pin "1") (pinfunction "RE3/MCLR#/VPP_1") (pintype "unspecified"))
    )
    (net (code "59") (name "Net-(U2-A0)") (class "Default")
      (node (ref "R27") (pin "2") (pinfunction "2_2") (pintype "unspecified"))
      (node (ref "U16") (pin "1") (pinfunction "1_1") (pintype "unspecified"))
      (node (ref "U2") (pin "13") (pinfunction "A0_13") (pintype "unspecified"))
    )
    (net (code "60") (name "Net-(U2-A1)") (class "Default")
      (node (ref "R26") (pin "2") (pinfunction "2_2") (pintype "unspecified"))
      (node (ref "U15") (pin "1") (pinfunction "1_1") (pintype "unspecified"))
      (node (ref "U2") (pin "14") (pinfunction "A1_14") (pintype "unspecified"))
    )
    (net (code "61") (name "Net-(U2-A2)") (class "Default")
      (node (ref "R25") (pin "2") (pinfunction "2_2") (pintype "unspecified"))
      (node (ref "U14") (pin "1") (pinfunction "1_1") (pintype "unspecified"))
      (node (ref "U2") (pin "15") (pinfunction "A2_15") (pintype "unspecified"))
    )
    (net (code "62") (name "Net-(U2-A3)") (class "Default")
      (node (ref "R28") (pin "2") (pinfunction "2_2") (pintype "unspecified"))
      (node (ref "U17") (pin "1") (pinfunction "1_1") (pintype "unspecified"))
      (node (ref "U2") (pin "12") (pinfunction "A3_12") (pintype "unspecified"))
    )
    (net (code "63") (name "Net-(U2-A4)") (class "Default")
      (node (ref "R24") (pin "2") (pinfunction "2_2") (pintype "unspecified"))
      (node (ref "U13") (pin "1") (pinfunction "1_1") (pintype "unspecified"))
      (node (ref "U2") (pin "1") (pinfunction "A4_1") (pintype "unspecified"))
    )
    (net (code "64") (name "Net-(U3-C1+)") (class "Default")
      (node (ref "C16") (pin "2") (pinfunction "2_2") (pintype "unspecified"))
      (node (ref "U3") (pin "1") (pinfunction "C1+_1") (pintype "unspecified"))
    )
    (net (code "65") (name "Net-(U3-C1-)") (class "Default")
      (node (ref "C16") (pin "1") (pinfunction "1_1") (pintype "unspecified"))
      (node (ref "U3") (pin "3") (pinfunction "C1-_3") (pintype "unspecified"))
    )
    (net (code "66") (name "Net-(U3-C2+)") (class "Default")
      (node (ref "C18") (pin "2") (pinfunction "2_2") (pintype "unspecified"))
      (node (ref "U3") (pin "4") (pinfunction "C2+_4") (pintype "unspecified"))
    )
    (net (code "67") (name "Net-(U3-C2-)") (class "Default")
      (node (ref "C18") (pin "1") (pinfunction "1_1") (pintype "unspecified"))
      (node (ref "U3") (pin "5") (pinfunction "C2-_5") (pintype "unspecified"))
    )
    (net (code "68") (name "Net-(U3-R1IN)") (class "Default")
      (node (ref "H7") (pin "2") (pinfunction "2_2") (pintype "unspecified"))
      (node (ref "U3") (pin "13") (pinfunction "R1IN_13") (pintype "unspecified"))
    )
    (net (code "69") (name "Net-(U3-R2IN)") (class "Default")
      (node (ref "H7") (pin "4") (pinfunction "4_4") (pintype "unspecified"))
      (node (ref "U3") (pin "8") (pinfunction "R2IN_8") (pintype "unspecified"))
    )
    (net (code "70") (name "Net-(U3-T1OUT)") (class "Default")
      (node (ref "H7") (pin "3") (pinfunction "3_3") (pintype "unspecified"))
      (node (ref "U3") (pin "14") (pinfunction "T1OUT_14") (pintype "unspecified"))
    )
    (net (code "71") (name "Net-(U3-T2OUT)") (class "Default")
      (node (ref "H7") (pin "5") (pinfunction "5_5") (pintype "unspecified"))
      (node (ref "U3") (pin "7") (pinfunction "T2OUT_7") (pintype "unspecified"))
    )
    (net (code "72") (name "Net-(U3-V+)") (class "Default")
      (node (ref "C17") (pin "1") (pinfunction "1_1") (pintype "unspecified"))
      (node (ref "U3") (pin "2") (pinfunction "V+_2") (pintype "unspecified"))
    )
    (net (code "73") (name "Net-(U3-V-)") (class "Default")
      (node (ref "C19") (pin "2") (pinfunction "2_2") (pintype "unspecified"))
      (node (ref "U3") (pin "6") (pinfunction "V-_6") (pintype "unspecified"))
    )
    (net (code "74") (name "Net-(U4-P0)") (class "Default")
      (node (ref "R29") (pin "1") (pinfunction "1_1") (pintype "unspecified"))
      (node (ref "U29") (pin "2") (pinfunction "2_2") (pintype "unspecified"))
      (node (ref "U4") (pin "4") (pinfunction "P0_4") (pintype "unspecified"))
    )
    (net (code "75") (name "Net-(U4-P1)") (class "Default")
      (node (ref "R30") (pin "1") (pinfunction "1_1") (pintype "unspecified"))
      (node (ref "U20") (pin "2") (pinfunction "2_2") (pintype "unspecified"))
      (node (ref "U4") (pin "5") (pinfunction "P1_5") (pintype "unspecified"))
    )
    (net (code "76") (name "Net-(U4-P2)") (class "Default")
      (node (ref "R31") (pin "1") (pinfunction "1_1") (pintype "unspecified"))
      (node (ref "U21") (pin "2") (pinfunction "2_2") (pintype "unspecified"))
      (node (ref "U4") (pin "6") (pinfunction "P2_6") (pintype "unspecified"))
    )
    (net (code "77") (name "Net-(U4-P3)") (class "Default")
      (node (ref "R32") (pin "1") (pinfunction "1_1") (pintype "unspecified"))
      (node (ref "U22") (pin "2") (pinfunction "2_2") (pintype "unspecified"))
      (node (ref "U4") (pin "7") (pinfunction "P3_7") (pintype "unspecified"))
    )
    (net (code "78") (name "Net-(U4-P4)") (class "Default")
      (node (ref "R33") (pin "1") (pinfunction "1_1") (pintype "unspecified"))
      (node (ref "U23") (pin "2") (pinfunction "2_2") (pintype "unspecified"))
      (node (ref "U4") (pin "9") (pinfunction "P4_9") (pintype "unspecified"))
    )
    (net (code "79") (name "Net-(U4-P5)") (class "Default")
      (node (ref "R34") (pin "1") (pinfunction "1_1") (pintype "unspecified"))
      (node (ref "U24") (pin "2") (pinfunction "2_2") (pintype "unspecified"))
      (node (ref "U4") (pin "10") (pinfunction "P5_10") (pintype "unspecified"))
    )
    (net (code "80") (name "Net-(U4-P6)") (class "Default")
      (node (ref "R35") (pin "1") (pinfunction "1_1") (pintype "unspecified"))
      (node (ref "U25") (pin "2") (pinfunction "2_2") (pintype "unspecified"))
      (node (ref "U4") (pin "11") (pinfunction "P6_11") (pintype "unspecified"))
    )
    (net (code "81") (name "Net-(U4-P7)") (class "Default")
      (node (ref "R36") (pin "1") (pinfunction "1_1") (pintype "unspecified"))
      (node (ref "U26") (pin "2") (pinfunction "2_2") (pintype "unspecified"))
      (node (ref "U4") (pin "12") (pinfunction "P7_12") (pintype "unspecified"))
    )
    (net (code "82") (name "Net-(U5-A0)") (class "Default")
      (node (ref "R15") (pin "1") (pinfunction "1_1") (pintype "unspecified"))
      (node (ref "U5") (pin "1") (pinfunction "A0_1") (pintype "unspecified"))
    )
    (net (code "83") (name "Net-(U5-P0)") (class "Default")
      (node (ref "R37") (pin "1") (pinfunction "1_1") (pintype "unspecified"))
      (node (ref "U27") (pin "2") (pinfunction "2_2") (pintype "unspecified"))
      (node (ref "U5") (pin "4") (pinfunction "P0_4") (pintype "unspecified"))
    )
    (net (code "84") (name "Net-(U5-P1)") (class "Default")
      (node (ref "R38") (pin "1") (pinfunction "1_1") (pintype "unspecified"))
      (node (ref "U28") (pin "2") (pinfunction "2_2") (pintype "unspecified"))
      (node (ref "U5") (pin "5") (pinfunction "P1_5") (pintype "unspecified"))
    )
    (net (code "85") (name "Net-(U5-P2)") (class "Default")
      (node (ref "R39") (pin "2") (pinfunction "2_2") (pintype "unspecified"))
      (node (ref "U30") (pin "2") (pinfunction "2_2") (pintype "unspecified"))
      (node (ref "U5") (pin "6") (pinfunction "P2_6") (pintype "unspecified"))
    )
    (net (code "86") (name "Net-(U5-P3)") (class "Default")
      (node (ref "H5") (pin "9") (pinfunction "9_9") (pintype "unspecified"))
      (node (ref "U5") (pin "7") (pinfunction "P3_7") (pintype "unspecified"))
    )
    (net (code "87") (name "Net-(U5-P4)") (class "Default")
      (node (ref "H5") (pin "7") (pinfunction "7_7") (pintype "unspecified"))
      (node (ref "U5") (pin "9") (pinfunction "P4_9") (pintype "unspecified"))
    )
    (net (code "88") (name "Net-(U5-P5)") (class "Default")
      (node (ref "H5") (pin "5") (pinfunction "5_5") (pintype "unspecified"))
      (node (ref "U5") (pin "10") (pinfunction "P5_10") (pintype "unspecified"))
    )
    (net (code "89") (name "Net-(U5-P6)") (class "Default")
      (node (ref "H5") (pin "3") (pinfunction "3_3") (pintype "unspecified"))
      (node (ref "U5") (pin "11") (pinfunction "P6_11") (pintype "unspecified"))
    )
    (net (code "90") (name "Net-(U5-P7)") (class "Default")
      (node (ref "H5") (pin "1") (pinfunction "1_1") (pintype "unspecified"))
      (node (ref "U5") (pin "12") (pinfunction "P7_12") (pintype "unspecified"))
    )
    (net (code "91") (name "Net-(U19-A0)") (class "Default")
      (node (ref "R22") (pin "2") (pinfunction "2_2") (pintype "unspecified"))
      (node (ref "U11") (pin "1") (pinfunction "1_1") (pintype "unspecified"))
      (node (ref "U19") (pin "13") (pinfunction "A0_13") (pintype "unspecified"))
    )
    (net (code "92") (name "Net-(U19-A1)") (class "Default")
      (node (ref "R21") (pin "2") (pinfunction "2_2") (pintype "unspecified"))
      (node (ref "U10") (pin "1") (pinfunction "1_1") (pintype "unspecified"))
      (node (ref "U19") (pin "14") (pinfunction "A1_14") (pintype "unspecified"))
    )
    (net (code "93") (name "Net-(U19-A2)") (class "Default")
      (node (ref "R20") (pin "2") (pinfunction "2_2") (pintype "unspecified"))
      (node (ref "U19") (pin "15") (pinfunction "A2_15") (pintype "unspecified"))
      (node (ref "U9") (pin "1") (pinfunction "1_1") (pintype "unspecified"))
    )
    (net (code "94") (name "Net-(U19-A3)") (class "Default")
      (node (ref "R23") (pin "2") (pinfunction "2_2") (pintype "unspecified"))
      (node (ref "U12") (pin "1") (pinfunction "1_1") (pintype "unspecified"))
      (node (ref "U19") (pin "12") (pinfunction "A3_12") (pintype "unspecified"))
    )
    (net (code "95") (name "Net-(U19-A4)") (class "Default")
      (node (ref "R19") (pin "2") (pinfunction "2_2") (pintype "unspecified"))
      (node (ref "U19") (pin "1") (pinfunction "A4_1") (pintype "unspecified"))
      (node (ref "U8") (pin "1") (pinfunction "1_1") (pintype "unspecified"))
    )
    (net (code "96") (name "Net-(U19-A5)") (class "Default")
      (node (ref "R16") (pin "2") (pinfunction "2_2") (pintype "unspecified"))
      (node (ref "U18") (pin "1") (pinfunction "1_1") (pintype "unspecified"))
      (node (ref "U19") (pin "5") (pinfunction "A5_5") (pintype "unspecified"))
    )
    (net (code "97") (name "Net-(U19-A6)") (class "Default")
      (node (ref "R18") (pin "2") (pinfunction "2_2") (pintype "unspecified"))
      (node (ref "U19") (pin "2") (pinfunction "A6_2") (pintype "unspecified"))
      (node (ref "U7") (pin "1") (pinfunction "1_1") (pintype "unspecified"))
    )
    (net (code "98") (name "Net-(U19-A7)") (class "Default")
      (node (ref "R17") (pin "2") (pinfunction "2_2") (pintype "unspecified"))
      (node (ref "U19") (pin "4") (pinfunction "A7_4") (pintype "unspecified"))
      (node (ref "U6") (pin "1") (pinfunction "1_1") (pintype "unspecified"))
    )
    (net (code "99") (name "VCC") (class "Default")
      (node (ref "D1") (pin "1") (pinfunction "K_1") (pintype "unspecified"))
      (node (ref "D10") (pin "1") (pinfunction "K_1") (pintype "unspecified"))
      (node (ref "D11") (pin "1") (pinfunction "K_1") (pintype "unspecified"))
      (node (ref "D12") (pin "1") (pinfunction "K_1") (pintype "unspecified"))
      (node (ref "D13") (pin "1") (pinfunction "K_1") (pintype "unspecified"))
      (node (ref "D2") (pin "1") (pinfunction "K_1") (pintype "unspecified"))
      (node (ref "D3") (pin "1") (pinfunction "K_1") (pintype "unspecified"))
      (node (ref "D4") (pin "1") (pinfunction "K_1") (pintype "unspecified"))
      (node (ref "D5") (pin "1") (pinfunction "K_1") (pintype "unspecified"))
      (node (ref "D6") (pin "1") (pinfunction "K_1") (pintype "unspecified"))
      (node (ref "D7") (pin "1") (pinfunction "K_1") (pintype "unspecified"))
      (node (ref "D8") (pin "1") (pinfunction "K_1") (pintype "unspecified"))
      (node (ref "D9") (pin "1") (pinfunction "K_1") (pintype "unspecified"))
      (node (ref "U31") (pin "1") (pinfunction "1_1") (pintype "unspecified"))
      (node (ref "U32") (pin "1") (pinfunction "1_1") (pintype "unspecified"))
      (node (ref "U33") (pin "2") (pinfunction "2_2") (pintype "unspecified"))
      (node (ref "U34") (pin "2") (pinfunction "2_2") (pintype "unspecified"))
      (node (ref "U35") (pin "2") (pinfunction "2_2") (pintype "unspecified"))
      (node (ref "U36") (pin "2") (pinfunction "2_2") (pintype "unspecified"))
      (node (ref "U37") (pin "2") (pinfunction "2_2") (pintype "unspecified"))
      (node (ref "U38") (pin "2") (pinfunction "2_2") (pintype "unspecified"))
      (node (ref "U39") (pin "2") (pinfunction "2_2") (pintype "unspecified"))
      (node (ref "U40") (pin "2") (pinfunction "2_2") (pintype "unspecified"))
      (node (ref "U41") (pin "2") (pinfunction "2_2") (pintype "unspecified"))
      (node (ref "U42") (pin "2") (pinfunction "2_2") (pintype "unspecified"))
      (node (ref "U43") (pin "2") (pinfunction "2_2") (pintype "unspecified"))
      (node (ref "U44") (pin "2") (pinfunction "2_2") (pintype "unspecified"))
      (node (ref "U45") (pin "2") (pinfunction "2_2") (pintype "unspecified"))
      (node (ref "U46") (pin "2") (pinfunction "2_2") (pintype "unspecified"))
    )
    (net (code "100") (name "unconnected-(U1-RB5{slash}AN13{slash}T1G#-Pad38)") (class "Default")
      (node (ref "U1") (pin "38") (pinfunction "RB5/AN13/T1G#_38") (pintype "unspecified"))
    )
    (net (code "101") (name "unconnected-(U1-RC2{slash}P1A{slash}CCP1-Pad17)") (class "Default")
      (node (ref "U1") (pin "17") (pinfunction "RC2/P1A/CCP1_17") (pintype "unspecified"))
    )
    (net (code "102") (name "unconnected-(U1-RE0{slash}AN5-Pad8)") (class "Default")
      (node (ref "U1") (pin "8") (pinfunction "RE0/AN5_8") (pintype "unspecified"))
    )
    (net (code "103") (name "unconnected-(U1-RE1{slash}AN6-Pad9)") (class "Default")
      (node (ref "U1") (pin "9") (pinfunction "RE1/AN6_9") (pintype "unspecified"))
    )
    (net (code "104") (name "unconnected-(U1-RE2{slash}AN7-Pad10)") (class "Default")
      (node (ref "U1") (pin "10") (pinfunction "RE2/AN7_10") (pintype "unspecified"))
    )
  )
)
